# Recupera_ao.net
KiCad netlist of a schematic drawn in EAGLE
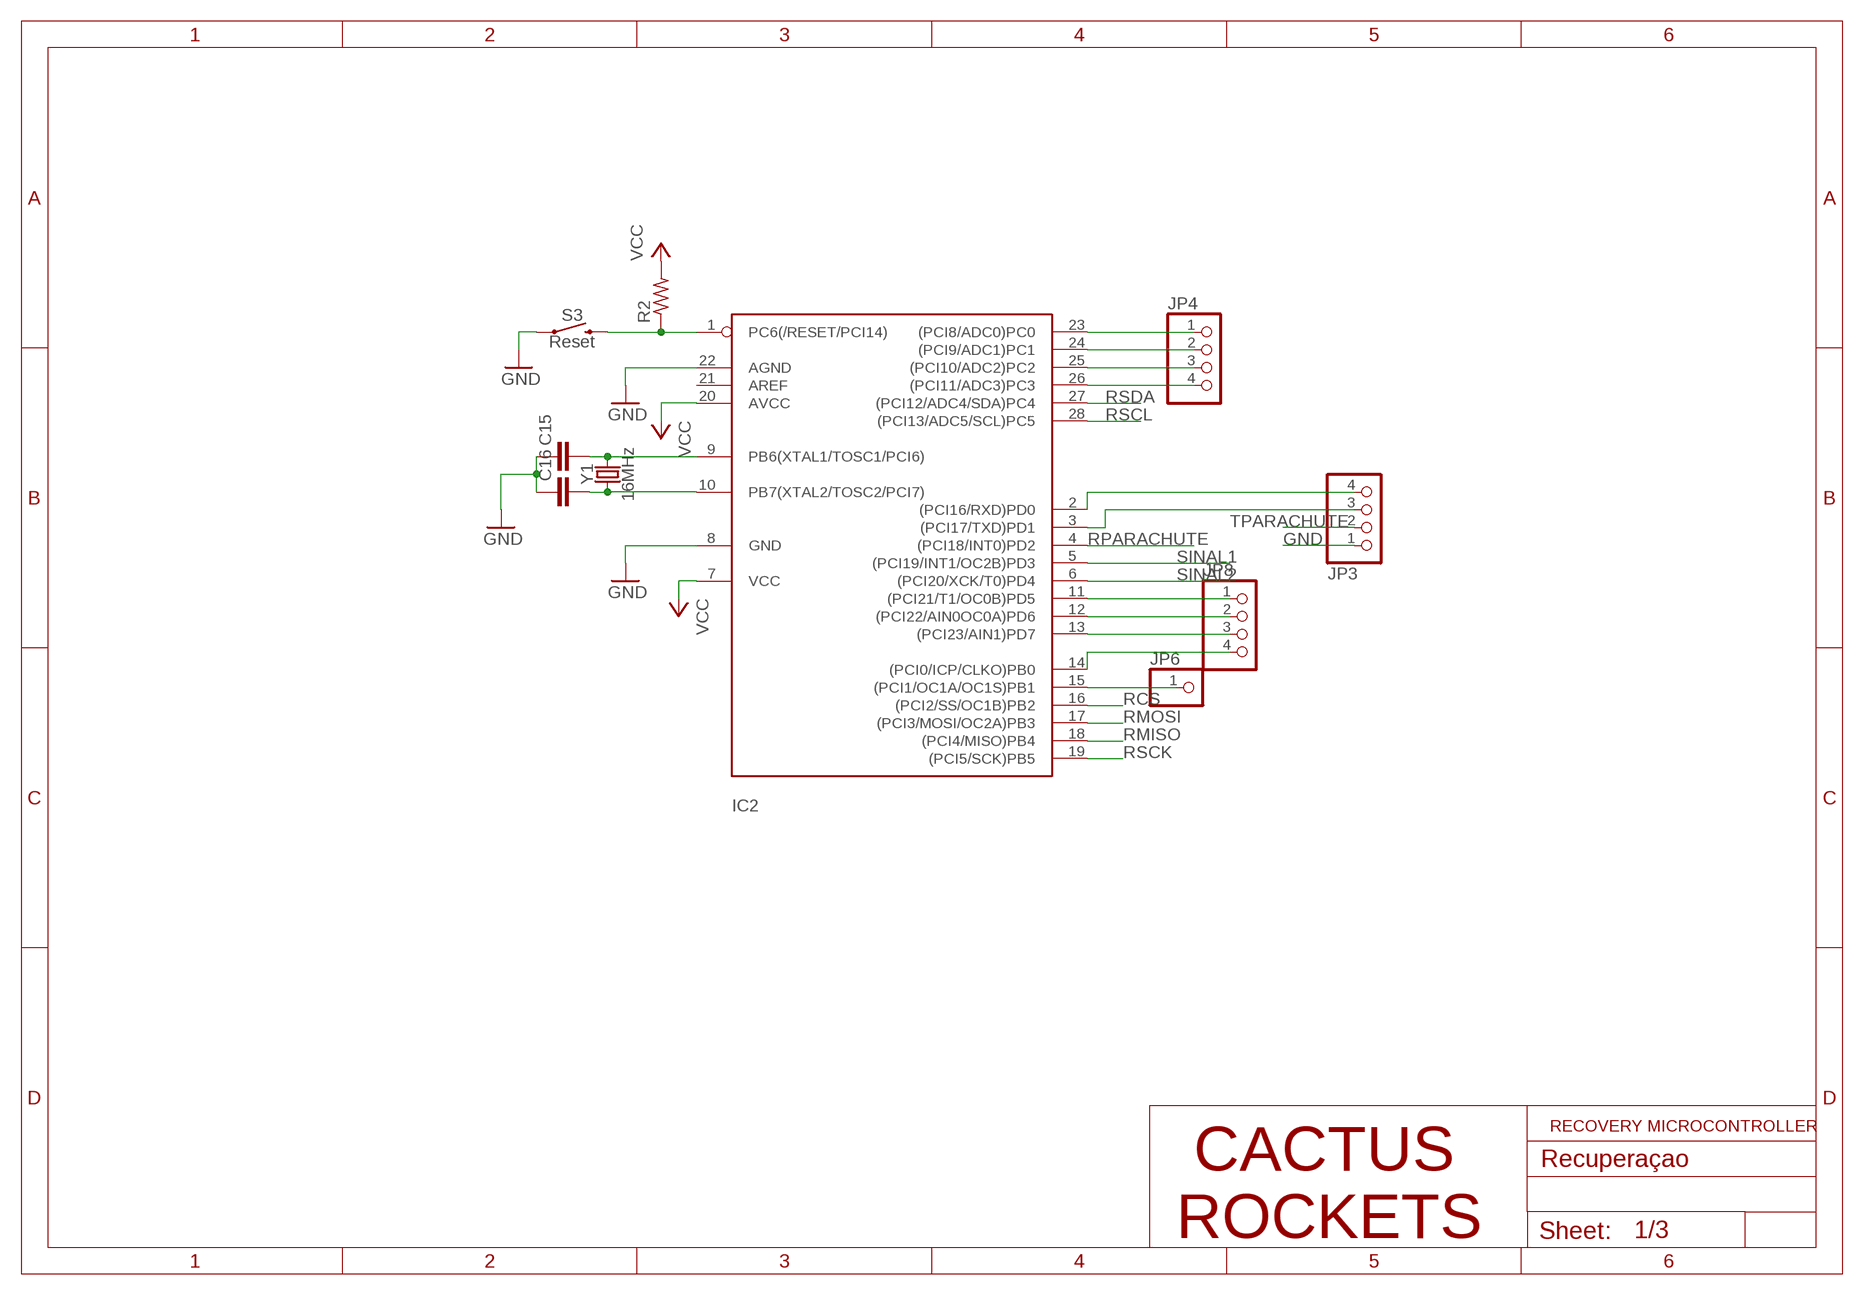
[diagram p0: schematic, sheet 1]
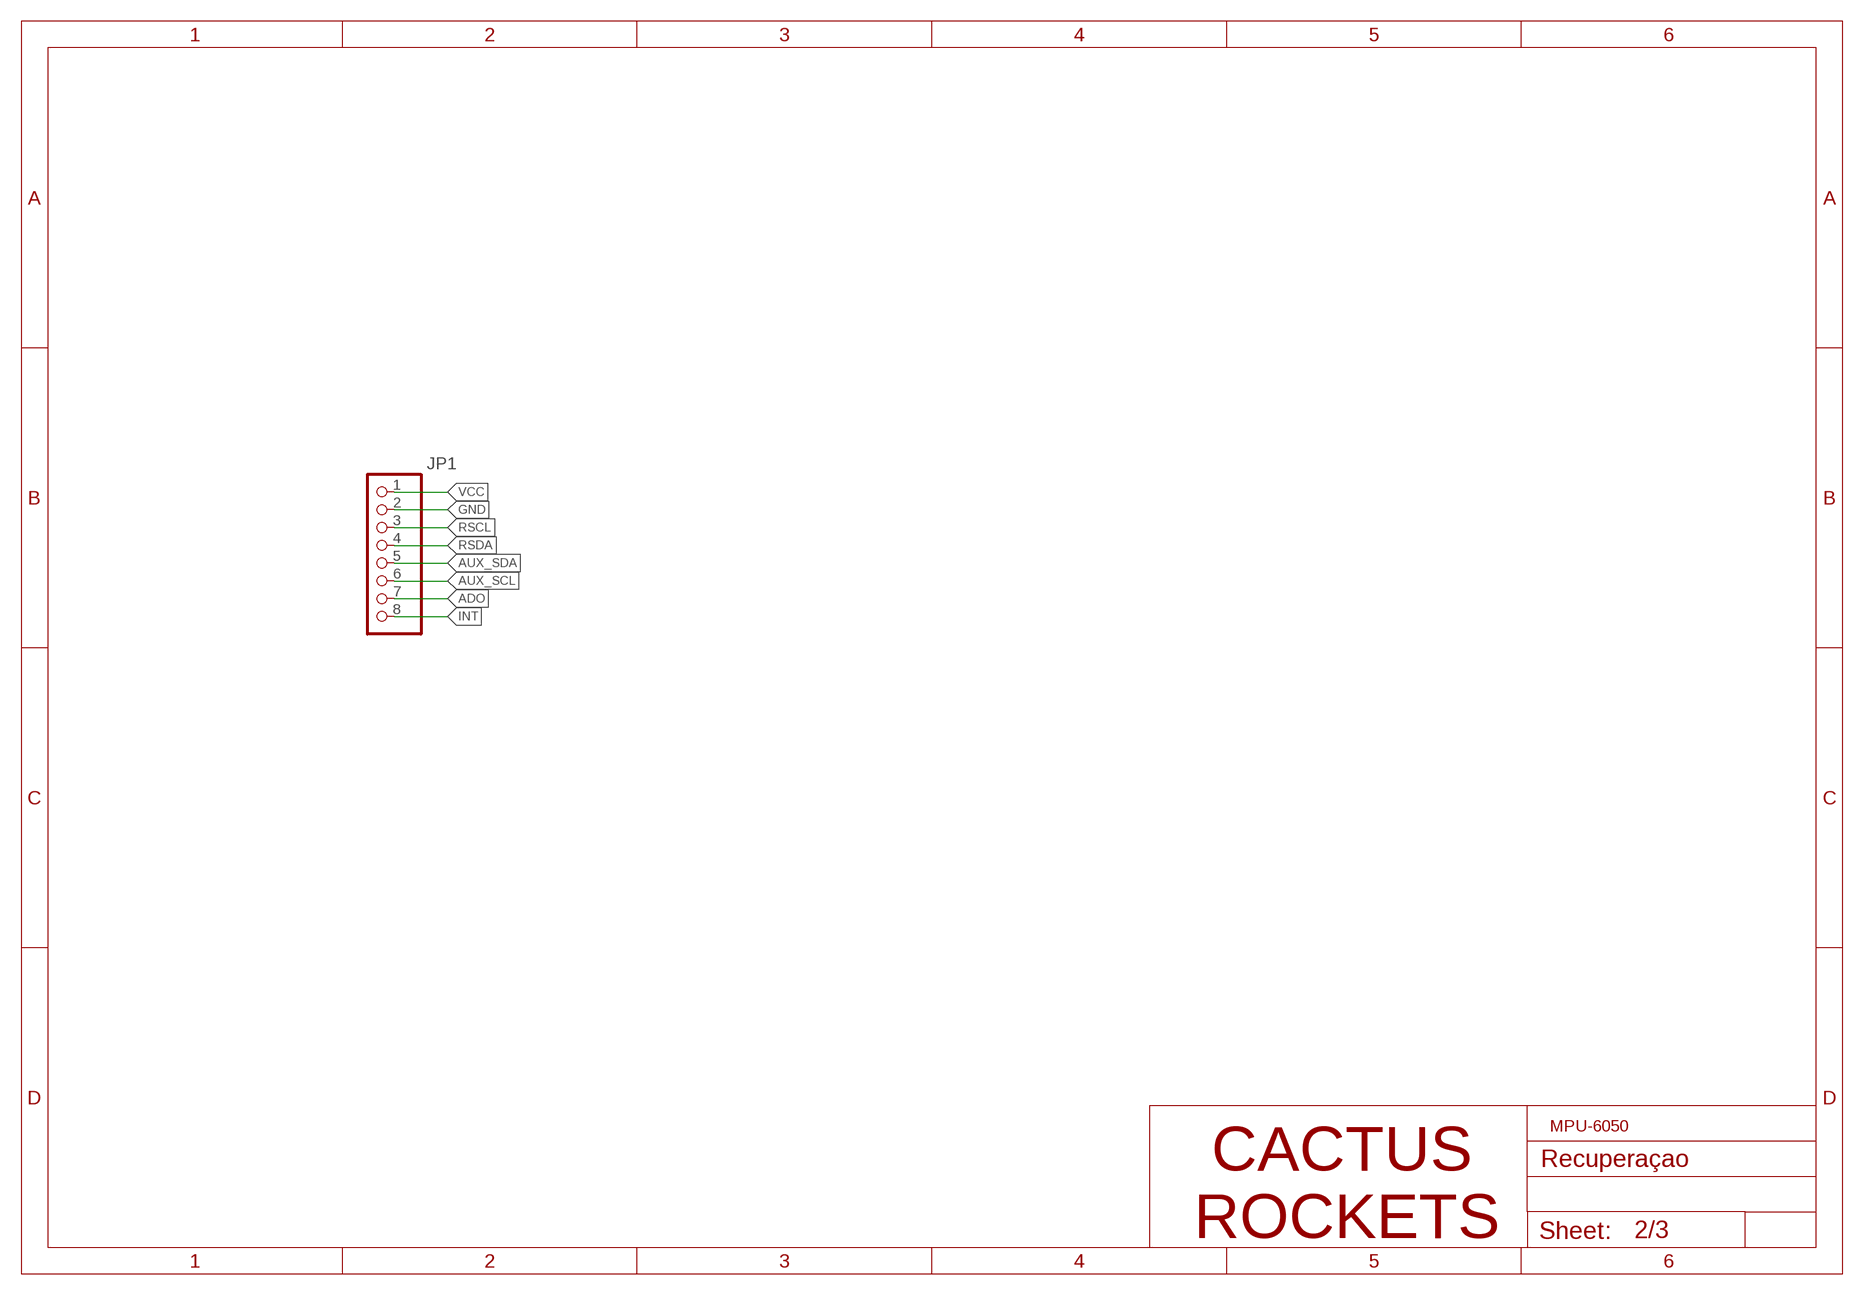
[diagram p1: schematic, sheet 2]
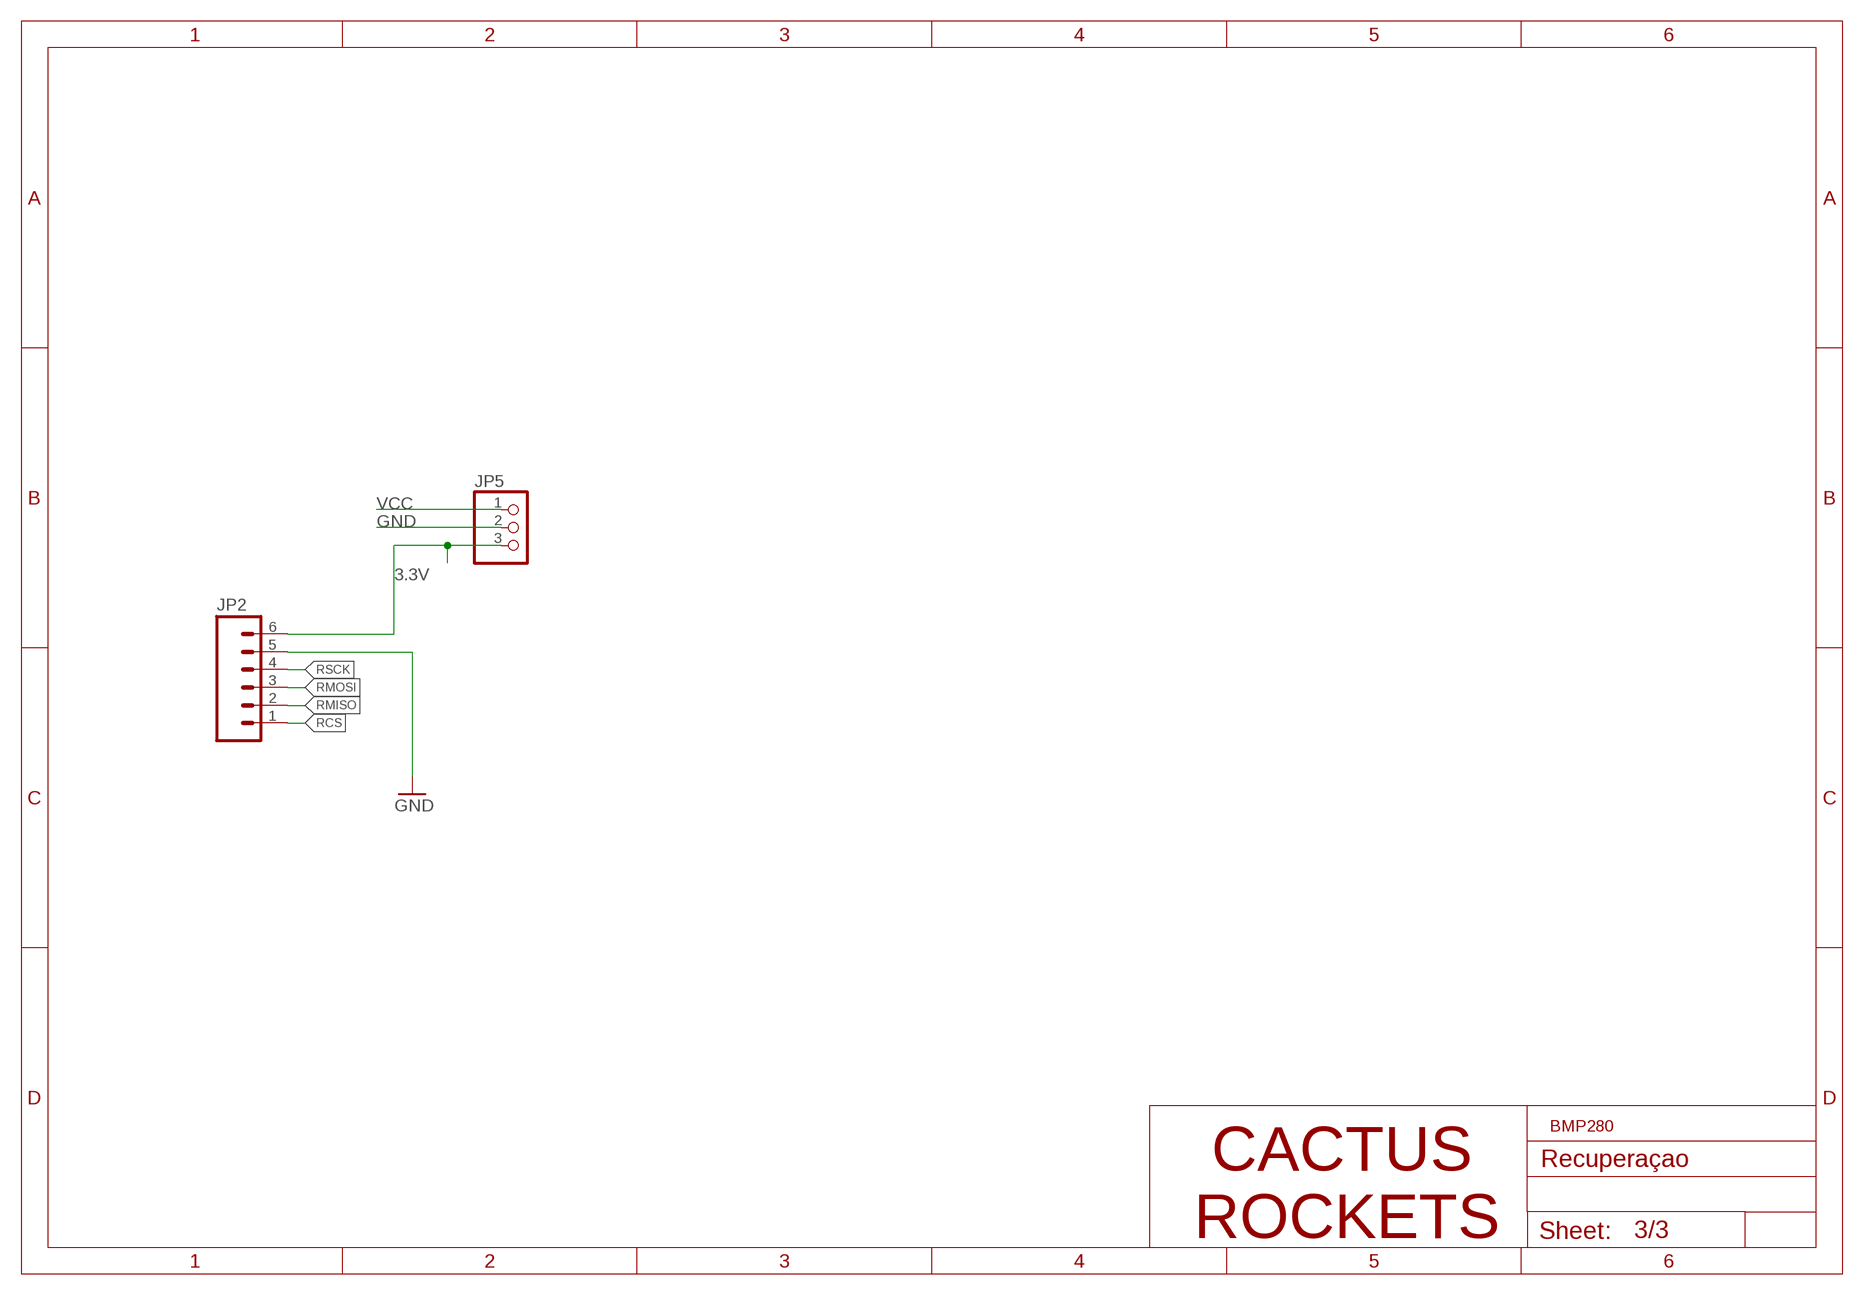
[diagram p2: schematic, sheet 3]

(export (version "E")
  (design (tool "Eeschema 10.0.6"))
  (components
    (comp (ref "JP2")
      (value "M06NO_SILK_FEMALE_PTH")
      (footprint "eagle-import:1X06_NO_SILK")
      (libsource (lib "eagle-import") (part "M06NO_SILK_FEMALE_PTH"))
    )
    (comp (ref "JP5")
      (value "PINHD-1X3/90")
      (footprint "eagle-import:1X03_90")
      (libsource (lib "eagle-import") (part "PINHD-1X3/90"))
    )
    (comp (ref "JP1")
      (value "PINHD-1X8")
      (footprint "eagle-import:1X08")
      (libsource (lib "eagle-import") (part "PINHD-1X8"))
    )
    (comp (ref "C15")
      (value "C-EU025-025X050")
      (footprint "eagle-import:C025-025X050")
      (libsource (lib "eagle-import") (part "C-EU025-025X050"))
    )
    (comp (ref "C16")
      (value "C-EU025-025X050")
      (footprint "eagle-import:C025-025X050")
      (libsource (lib "eagle-import") (part "C-EU025-025X050"))
    )
    (comp (ref "IC2")
      (value "ATMEGA328-20P")
      (footprint "eagle-import:DIL28-3")
      (libsource (lib "eagle-import") (part "ATMEGA328P-20"))
    )
    (comp (ref "JP3")
      (value "PINHD-1X4/90")
      (footprint "eagle-import:1X04_90")
      (libsource (lib "eagle-import") (part "PINHD-1X4/90"))
    )
    (comp (ref "JP4")
      (value "PINHD-1X4")
      (footprint "eagle-import:1X04")
      (libsource (lib "eagle-import") (part "PINHD-1X4"))
    )
    (comp (ref "JP6")
      (value "PINHD-1X1")
      (footprint "eagle-import:1X01")
      (libsource (lib "eagle-import") (part "PINHD-1X1"))
    )
    (comp (ref "JP8")
      (value "PINHD-1X4")
      (footprint "eagle-import:1X04")
      (libsource (lib "eagle-import") (part "PINHD-1X4"))
    )
    (comp (ref "R2")
      (value "R-US_0207/10")
      (footprint "eagle-import:0207_10")
      (libsource (lib "eagle-import") (part "R-US_0207/10"))
    )
    (comp (ref "S3")
      (value "Reset")
      (footprint "eagle-import:TACTILE_SWITCH_PTH_6.0MM")
      (libsource (lib "eagle-import") (part "MOMENTARY-SWITCH-SPST-PTH-6.0MM"))
    )
    (comp (ref "Y1")
      (value "16MHz")
      (footprint "eagle-import:HC49US")
      (libsource (lib "eagle-import") (part "CRYSTAL-16MHZPTH-HC49US"))
    )
  )
  (nets
    (net (code "1") (name "3.3V") (class "Default")
      (node (ref "JP2") (pin "6") (pinfunction "6_6") (pintype "passive"))
      (node (ref "JP5") (pin "3") (pinfunction "3_3") (pintype "passive"))
    )
    (net (code "2") (name "ADO") (class "Default")
      (node (ref "JP1") (pin "7") (pinfunction "7_7") (pintype "passive"))
    )
    (net (code "3") (name "AUX_SCL") (class "Default")
      (node (ref "JP1") (pin "6") (pinfunction "6_6") (pintype "passive"))
    )
    (net (code "4") (name "AUX_SDA") (class "Default")
      (node (ref "JP1") (pin "5") (pinfunction "5_5") (pintype "passive"))
    )
    (net (code "5") (name "GND") (class "Default")
      (node (ref "C15") (pin "1") (pinfunction "1_1") (pintype "passive"))
      (node (ref "C16") (pin "1") (pinfunction "1_1") (pintype "passive"))
      (node (ref "IC2") (pin "22") (pinfunction "AGND_22") (pintype "bidirectional"))
      (node (ref "IC2") (pin "8") (pinfunction "GND_8") (pintype "bidirectional"))
      (node (ref "JP1") (pin "2") (pinfunction "2_2") (pintype "passive"))
      (node (ref "JP2") (pin "5") (pinfunction "5_5") (pintype "passive"))
      (node (ref "JP3") (pin "1") (pinfunction "1_1") (pintype "passive"))
      (node (ref "JP5") (pin "2") (pinfunction "2_2") (pintype "passive"))
      (node (ref "S3") (pin "1") (pinfunction "1_1") (pintype "passive"))
      (node (ref "S3") (pin "2") (pinfunction "1_2") (pintype "passive"))
    )
    (net (code "6") (name "INT") (class "Default")
      (node (ref "JP1") (pin "8") (pinfunction "8_8") (pintype "passive"))
    )
    (net (code "7") (name "Net-(IC2-(PCI0{slash}ICP{slash}CLKO)PB0)") (class "Default")
      (node (ref "IC2") (pin "14") (pinfunction "(PCI0/ICP/CLKO)PB0_14") (pintype "bidirectional"))
      (node (ref "JP8") (pin "4") (pinfunction "4_4") (pintype "passive"))
    )
    (net (code "8") (name "Net-(IC2-(PCI1{slash}OC1A{slash}OC1S)PB1)") (class "Default")
      (node (ref "IC2") (pin "15") (pinfunction "(PCI1/OC1A/OC1S)PB1_15") (pintype "bidirectional"))
      (node (ref "JP6") (pin "1") (pinfunction "1_1") (pintype "passive"))
    )
    (net (code "9") (name "Net-(IC2-(PCI8{slash}ADC0)PC0)") (class "Default")
      (node (ref "IC2") (pin "23") (pinfunction "(PCI8/ADC0)PC0_23") (pintype "bidirectional"))
      (node (ref "JP4") (pin "1") (pinfunction "1_1") (pintype "passive"))
    )
    (net (code "10") (name "Net-(IC2-(PCI9{slash}ADC1)PC1)") (class "Default")
      (node (ref "IC2") (pin "24") (pinfunction "(PCI9/ADC1)PC1_24") (pintype "bidirectional"))
      (node (ref "JP4") (pin "2") (pinfunction "2_2") (pintype "passive"))
    )
    (net (code "11") (name "Net-(IC2-(PCI10{slash}ADC2)PC2)") (class "Default")
      (node (ref "IC2") (pin "25") (pinfunction "(PCI10/ADC2)PC2_25") (pintype "bidirectional"))
      (node (ref "JP4") (pin "3") (pinfunction "3_3") (pintype "passive"))
    )
    (net (code "12") (name "Net-(IC2-(PCI11{slash}ADC3)PC3)") (class "Default")
      (node (ref "IC2") (pin "26") (pinfunction "(PCI11/ADC3)PC3_26") (pintype "bidirectional"))
      (node (ref "JP4") (pin "4") (pinfunction "4_4") (pintype "passive"))
    )
    (net (code "13") (name "Net-(IC2-(PCI16{slash}RXD)PD0)") (class "Default")
      (node (ref "IC2") (pin "2") (pinfunction "(PCI16/RXD)PD0_2") (pintype "bidirectional"))
      (node (ref "JP3") (pin "4") (pinfunction "4_4") (pintype "passive"))
    )
    (net (code "14") (name "Net-(IC2-(PCI17{slash}TXD)PD1)") (class "Default")
      (node (ref "IC2") (pin "3") (pinfunction "(PCI17/TXD)PD1_3") (pintype "bidirectional"))
      (node (ref "JP3") (pin "3") (pinfunction "3_3") (pintype "passive"))
    )
    (net (code "15") (name "Net-(IC2-(PCI21{slash}T1{slash}OC0B)PD5)") (class "Default")
      (node (ref "IC2") (pin "11") (pinfunction "(PCI21/T1/OC0B)PD5_11") (pintype "bidirectional"))
      (node (ref "JP8") (pin "1") (pinfunction "1_1") (pintype "passive"))
    )
    (net (code "16") (name "Net-(IC2-(PCI22{slash}AIN0OC0A)PD6)") (class "Default")
      (node (ref "IC2") (pin "12") (pinfunction "(PCI22/AIN0OC0A)PD6_12") (pintype "bidirectional"))
      (node (ref "JP8") (pin "2") (pinfunction "2_2") (pintype "passive"))
    )
    (net (code "17") (name "Net-(IC2-(PCI23{slash}AIN1)PD7)") (class "Default")
      (node (ref "IC2") (pin "13") (pinfunction "(PCI23/AIN1)PD7_13") (pintype "bidirectional"))
      (node (ref "JP8") (pin "3") (pinfunction "3_3") (pintype "passive"))
    )
    (net (code "18") (name "Net-(IC2-PB6(XTAL1{slash}TOSC1{slash}PCI6))") (class "Default")
      (node (ref "C15") (pin "2") (pinfunction "2_2") (pintype "passive"))
      (node (ref "IC2") (pin "9") (pinfunction "PB6(XTAL1/TOSC1/PCI6)_9") (pintype "bidirectional"))
      (node (ref "Y1") (pin "2") (pinfunction "2_2") (pintype "passive"))
    )
    (net (code "19") (name "Net-(IC2-PB7(XTAL2{slash}TOSC2{slash}PCI7))") (class "Default")
      (node (ref "C16") (pin "2") (pinfunction "2_2") (pintype "passive"))
      (node (ref "IC2") (pin "10") (pinfunction "PB7(XTAL2/TOSC2/PCI7)_10") (pintype "bidirectional"))
      (node (ref "Y1") (pin "1") (pinfunction "1_1") (pintype "passive"))
    )
    (net (code "20") (name "Net-(IC2-PC6({slash}RESET{slash}PCI14))") (class "Default")
      (node (ref "IC2") (pin "1") (pinfunction "PC6(/RESET/PCI14)_1") (pintype "bidirectional"))
      (node (ref "R2") (pin "1") (pinfunction "1_1") (pintype "passive"))
      (node (ref "S3") (pin "3") (pinfunction "2_3") (pintype "passive"))
      (node (ref "S3") (pin "4") (pinfunction "2_4") (pintype "passive"))
    )
    (net (code "21") (name "RCS") (class "Default")
      (node (ref "IC2") (pin "16") (pinfunction "(PCI2/SS/OC1B)PB2_16") (pintype "bidirectional"))
      (node (ref "JP2") (pin "1") (pinfunction "1_1") (pintype "passive"))
    )
    (net (code "22") (name "RMISO") (class "Default")
      (node (ref "IC2") (pin "18") (pinfunction "(PCI4/MISO)PB4_18") (pintype "bidirectional"))
      (node (ref "JP2") (pin "2") (pinfunction "2_2") (pintype "passive"))
    )
    (net (code "23") (name "RMOSI") (class "Default")
      (node (ref "IC2") (pin "17") (pinfunction "(PCI3/MOSI/OC2A)PB3_17") (pintype "bidirectional"))
      (node (ref "JP2") (pin "3") (pinfunction "3_3") (pintype "passive"))
    )
    (net (code "24") (name "RPARACHUTE") (class "Default")
      (node (ref "IC2") (pin "4") (pinfunction "(PCI18/INT0)PD2_4") (pintype "bidirectional"))
    )
    (net (code "25") (name "RSCK") (class "Default")
      (node (ref "IC2") (pin "19") (pinfunction "(PCI5/SCK)PB5_19") (pintype "bidirectional"))
      (node (ref "JP2") (pin "4") (pinfunction "4_4") (pintype "passive"))
    )
    (net (code "26") (name "RSCL") (class "Default")
      (node (ref "IC2") (pin "28") (pinfunction "(PCI13/ADC5/SCL)PC5_28") (pintype "bidirectional"))
      (node (ref "JP1") (pin "3") (pinfunction "3_3") (pintype "passive"))
    )
    (net (code "27") (name "RSDA") (class "Default")
      (node (ref "IC2") (pin "27") (pinfunction "(PCI12/ADC4/SDA)PC4_27") (pintype "bidirectional"))
      (node (ref "JP1") (pin "4") (pinfunction "4_4") (pintype "passive"))
    )
    (net (code "28") (name "SINAL1") (class "Default")
      (node (ref "IC2") (pin "5") (pinfunction "(PCI19/INT1/OC2B)PD3_5") (pintype "bidirectional"))
    )
    (net (code "29") (name "SINAL2") (class "Default")
      (node (ref "IC2") (pin "6") (pinfunction "(PCI20/XCK/T0)PD4_6") (pintype "bidirectional"))
    )
    (net (code "30") (name "TPARACHUTE") (class "Default")
      (node (ref "JP3") (pin "2") (pinfunction "2_2") (pintype "passive"))
    )
    (net (code "31") (name "VCC") (class "Default")
      (node (ref "IC2") (pin "20") (pinfunction "AVCC_20") (pintype "bidirectional"))
      (node (ref "IC2") (pin "7") (pinfunction "VCC_7") (pintype "bidirectional"))
      (node (ref "JP1") (pin "1") (pinfunction "1_1") (pintype "passive"))
      (node (ref "JP5") (pin "1") (pinfunction "1_1") (pintype "passive"))
      (node (ref "R2") (pin "2") (pinfunction "2_2") (pintype "passive"))
    )
    (net (code "32") (name "unconnected-(IC2-AREF-Pad21)") (class "Default")
      (node (ref "IC2") (pin "21") (pinfunction "AREF_21") (pintype "bidirectional"))
    )
  )
)
